# SCH_H-brug.net
KiCad netlist of a schematic drawn in EasyEDA
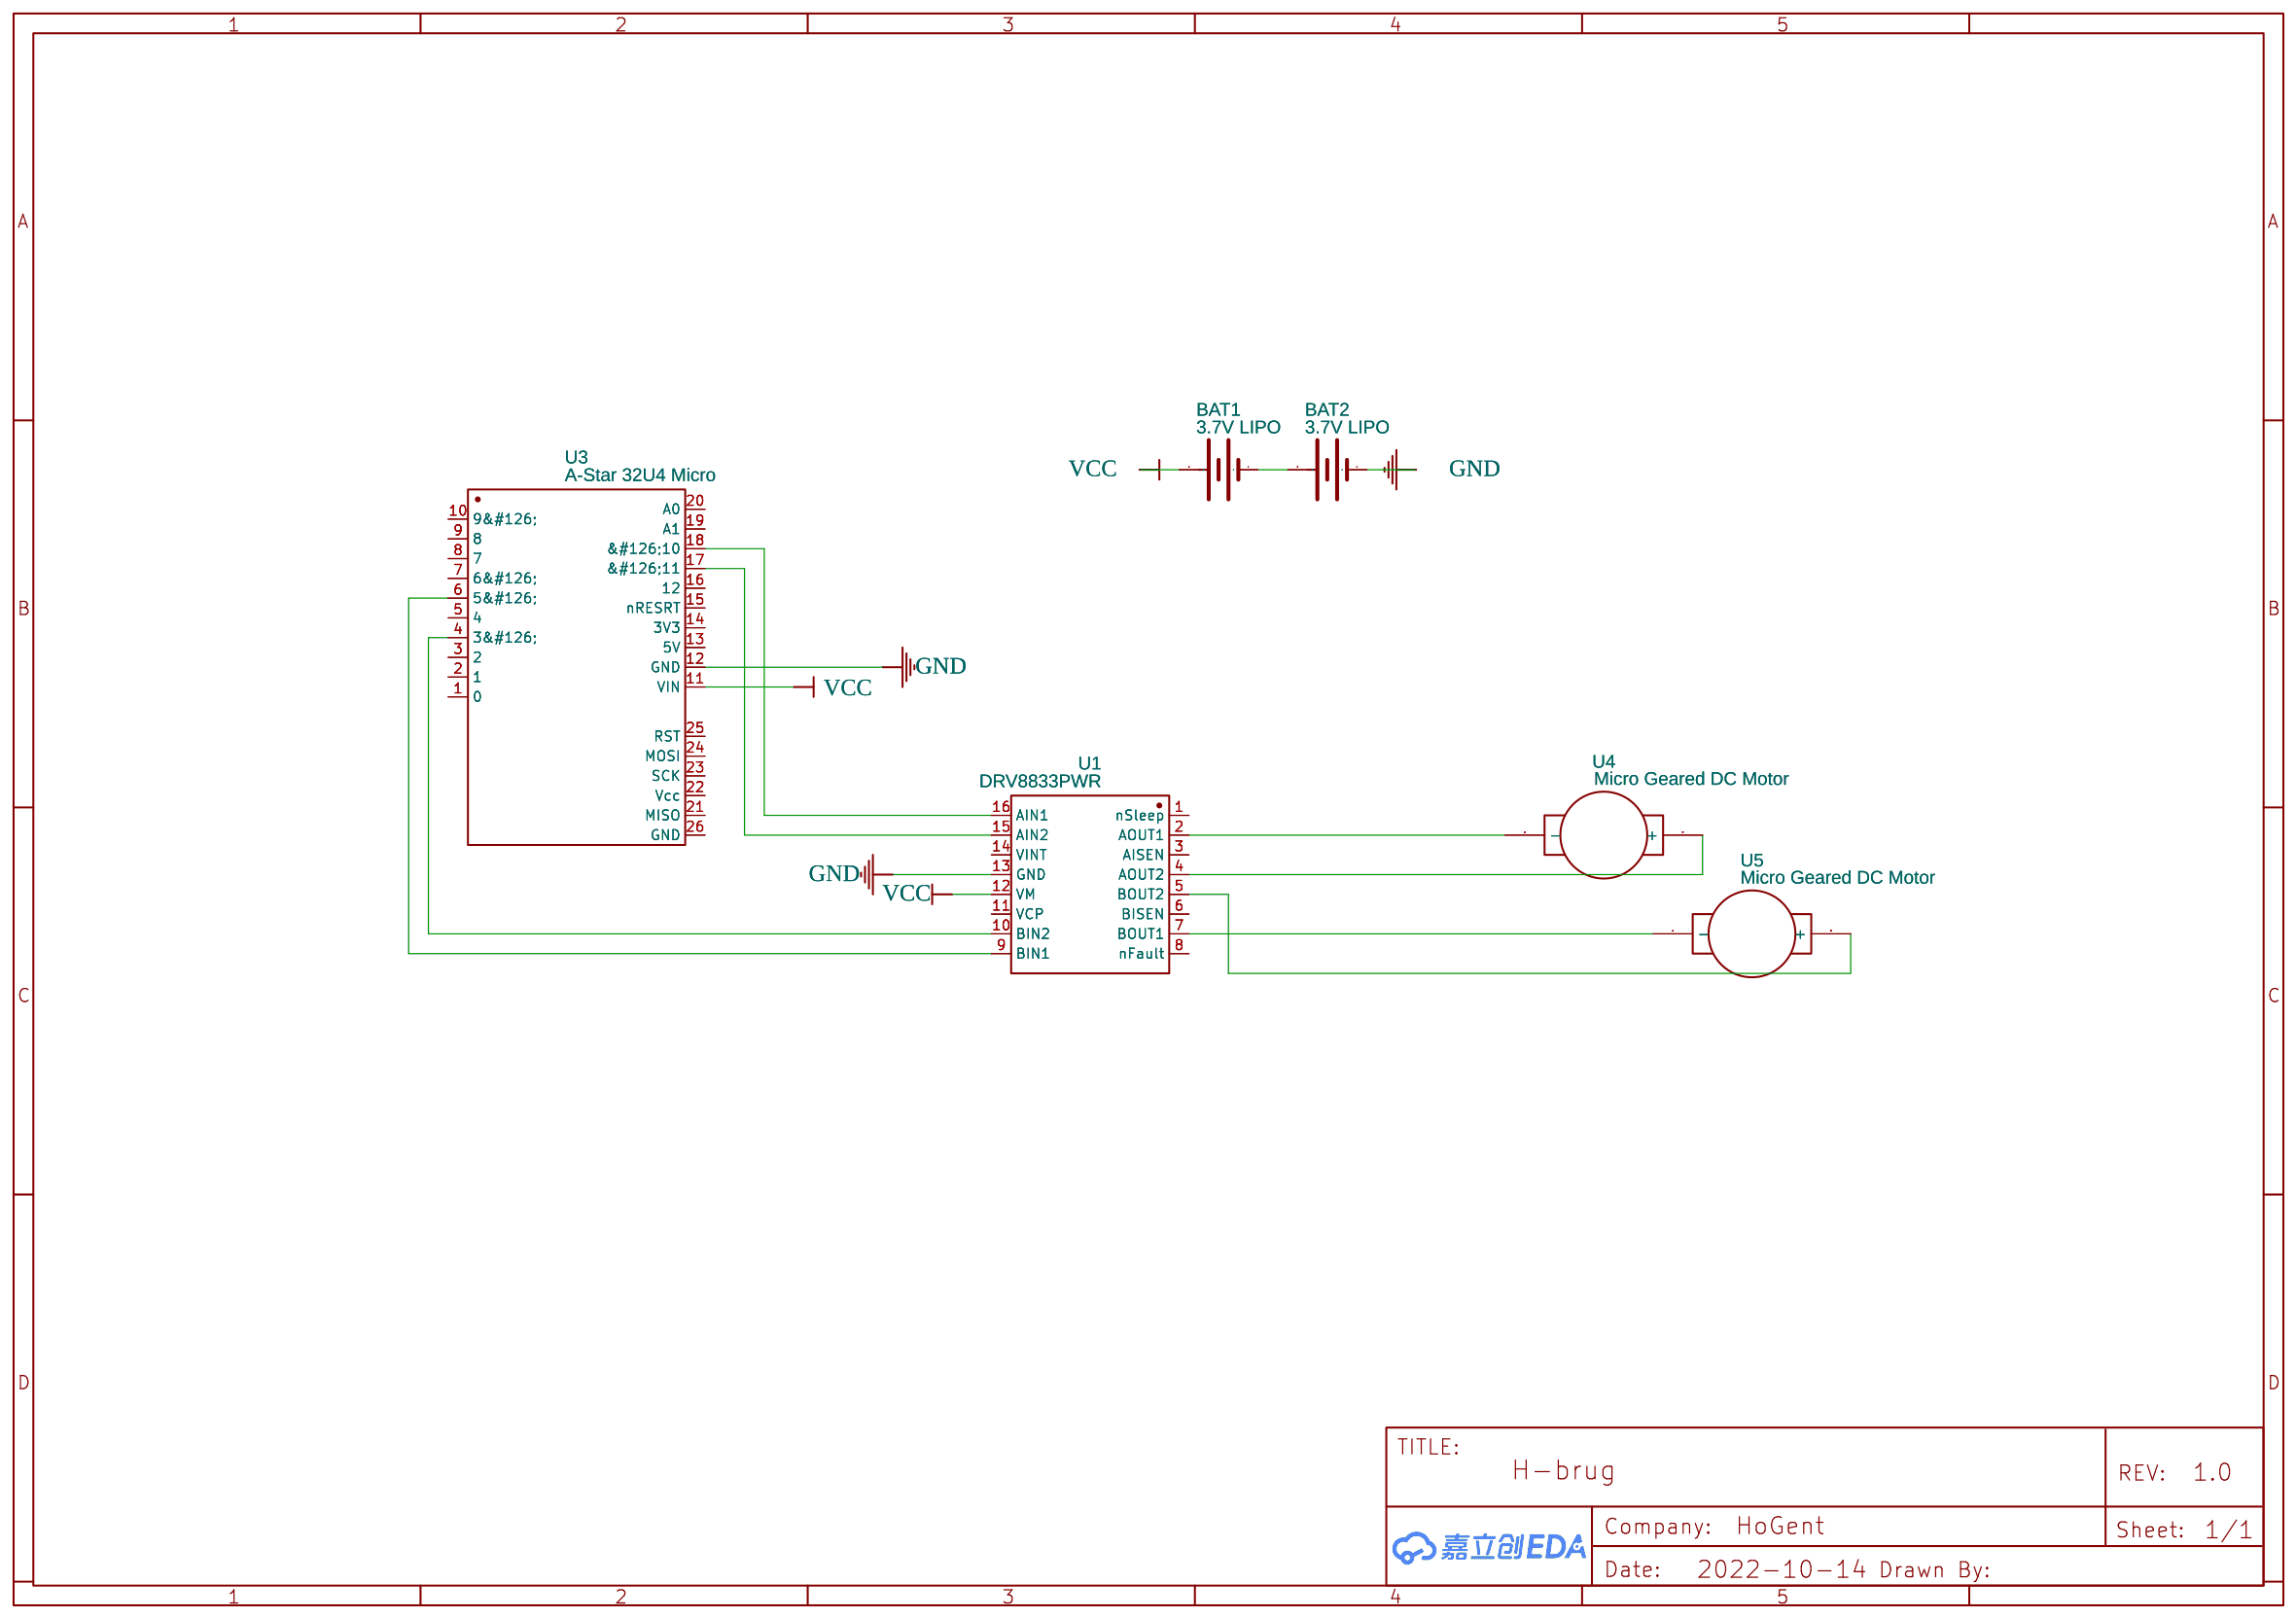
[diagram p0: schematic sheet]

(export (version "E")
  (design (tool "Eeschema 10.0.6"))
  (components
    (comp (ref "BAT1") (value "3.7V LIPO") (libsource (lib "") (part "3.7V LIPO")))
    (comp (ref "BAT2") (value "3.7V LIPO") (libsource (lib "") (part "3.7V LIPO")))
    (comp (ref "U1")
      (value "DRV8833PWR")
      (fields (field (name "BOM_Supplier Part") "C544801"))
      (libsource (lib "") (part "DRV8833PWR"))
    )
    (comp (ref "U3")
      (value "A-Star 32U4 Micro")
      (fields (field (name "BOM_Manufacturer Part") "3101"))
      (libsource (lib "") (part "A-Star 32U4 Micro"))
    )
    (comp (ref "U4") (value "Micro Geared DC Motor") (libsource (lib "") (part "Micro Geared DC Motor")))
    (comp (ref "U5") (value "Micro Geared DC Motor") (libsource (lib "") (part "Micro Geared DC Motor")))
  )
  (nets
    (net (code "1") (name "GND") (class "Default")
      (node (ref "BAT2") (pin "-") (pinfunction "-_-") (pintype "passive"))
      (node (ref "U1") (pin "13") (pinfunction "GND_13") (pintype "unspecified"))
      (node (ref "U3") (pin "12") (pinfunction "GND_12") (pintype "unspecified"))
    )
    (net (code "2") (name "Net-(BAT1-Pad-)") (class "Default")
      (node (ref "BAT1") (pin "-") (pinfunction "-_-") (pintype "passive"))
      (node (ref "BAT2") (pin "+") (pinfunction "+_+") (pintype "passive"))
    )
    (net (code "3") (name "Net-(U1-AIN1)") (class "Default")
      (node (ref "U1") (pin "16") (pinfunction "AIN1_16") (pintype "unspecified"))
      (node (ref "U3") (pin "18") (pinfunction "&#126;10_18") (pintype "unspecified"))
    )
    (net (code "4") (name "Net-(U1-AIN2)") (class "Default")
      (node (ref "U1") (pin "15") (pinfunction "AIN2_15") (pintype "unspecified"))
      (node (ref "U3") (pin "17") (pinfunction "&#126;11_17") (pintype "unspecified"))
    )
    (net (code "5") (name "Net-(U1-AOUT1)") (class "Default")
      (node (ref "U1") (pin "2") (pinfunction "AOUT1_2") (pintype "unspecified"))
      (node (ref "U4") (pin "1") (pinfunction "-_1") (pintype "unspecified"))
    )
    (net (code "6") (name "Net-(U1-AOUT2)") (class "Default")
      (node (ref "U1") (pin "4") (pinfunction "AOUT2_4") (pintype "unspecified"))
      (node (ref "U4") (pin "2") (pinfunction "+_2") (pintype "unspecified"))
    )
    (net (code "7") (name "Net-(U1-BIN1)") (class "Default")
      (node (ref "U1") (pin "9") (pinfunction "BIN1_9") (pintype "unspecified"))
      (node (ref "U3") (pin "6") (pinfunction "5&#126;_6") (pintype "unspecified"))
    )
    (net (code "8") (name "Net-(U1-BIN2)") (class "Default")
      (node (ref "U1") (pin "10") (pinfunction "BIN2_10") (pintype "unspecified"))
      (node (ref "U3") (pin "4") (pinfunction "3&#126;_4") (pintype "unspecified"))
    )
    (net (code "9") (name "Net-(U1-BOUT1)") (class "Default")
      (node (ref "U1") (pin "7") (pinfunction "BOUT1_7") (pintype "unspecified"))
      (node (ref "U5") (pin "1") (pinfunction "-_1") (pintype "unspecified"))
    )
    (net (code "10") (name "Net-(U1-BOUT2)") (class "Default")
      (node (ref "U1") (pin "5") (pinfunction "BOUT2_5") (pintype "unspecified"))
      (node (ref "U5") (pin "2") (pinfunction "+_2") (pintype "unspecified"))
    )
    (net (code "11") (name "VCC") (class "Default")
      (node (ref "BAT1") (pin "+") (pinfunction "+_+") (pintype "passive"))
      (node (ref "U1") (pin "12") (pinfunction "VM_12") (pintype "unspecified"))
      (node (ref "U3") (pin "11") (pinfunction "VIN_11") (pintype "unspecified"))
    )
    (net (code "12") (name "unconnected-(U1-AISEN-Pad3)") (class "Default")
      (node (ref "U1") (pin "3") (pinfunction "AISEN_3") (pintype "unspecified"))
    )
    (net (code "13") (name "unconnected-(U1-BISEN-Pad6)") (class "Default")
      (node (ref "U1") (pin "6") (pinfunction "BISEN_6") (pintype "unspecified"))
    )
    (net (code "14") (name "unconnected-(U1-VCP-Pad11)") (class "Default")
      (node (ref "U1") (pin "11") (pinfunction "VCP_11") (pintype "unspecified"))
    )
    (net (code "15") (name "unconnected-(U1-VINT-Pad14)") (class "Default")
      (node (ref "U1") (pin "14") (pinfunction "VINT_14") (pintype "unspecified"))
    )
    (net (code "16") (name "unconnected-(U1-nFault-Pad8)") (class "Default")
      (node (ref "U1") (pin "8") (pinfunction "nFault_8") (pintype "unspecified"))
    )
    (net (code "17") (name "unconnected-(U1-nSleep-Pad1)") (class "Default")
      (node (ref "U1") (pin "1") (pinfunction "nSleep_1") (pintype "unspecified"))
    )
    (net (code "18") (name "unconnected-(U3-0-Pad1)") (class "Default")
      (node (ref "U3") (pin "1") (pinfunction "0_1") (pintype "unspecified"))
    )
    (net (code "19") (name "unconnected-(U3-1-Pad2)") (class "Default")
      (node (ref "U3") (pin "2") (pinfunction "1_2") (pintype "unspecified"))
    )
    (net (code "20") (name "unconnected-(U3-2-Pad3)") (class "Default")
      (node (ref "U3") (pin "3") (pinfunction "2_3") (pintype "unspecified"))
    )
    (net (code "21") (name "unconnected-(U3-3V3-Pad14)") (class "Default")
      (node (ref "U3") (pin "14") (pinfunction "3V3_14") (pintype "unspecified"))
    )
    (net (code "22") (name "unconnected-(U3-4-Pad5)") (class "Default")
      (node (ref "U3") (pin "5") (pinfunction "4_5") (pintype "unspecified"))
    )
    (net (code "23") (name "unconnected-(U3-5V-Pad13)") (class "Default")
      (node (ref "U3") (pin "13") (pinfunction "5V_13") (pintype "unspecified"))
    )
    (net (code "24") (name "unconnected-(U3-6&#126;-Pad7)") (class "Default")
      (node (ref "U3") (pin "7") (pinfunction "6&#126;_7") (pintype "unspecified"))
    )
    (net (code "25") (name "unconnected-(U3-7-Pad8)") (class "Default")
      (node (ref "U3") (pin "8") (pinfunction "7_8") (pintype "unspecified"))
    )
    (net (code "26") (name "unconnected-(U3-8-Pad9)") (class "Default")
      (node (ref "U3") (pin "9") (pinfunction "8_9") (pintype "unspecified"))
    )
    (net (code "27") (name "unconnected-(U3-9&#126;-Pad10)") (class "Default")
      (node (ref "U3") (pin "10") (pinfunction "9&#126;_10") (pintype "unspecified"))
    )
    (net (code "28") (name "unconnected-(U3-12-Pad16)") (class "Default")
      (node (ref "U3") (pin "16") (pinfunction "12_16") (pintype "unspecified"))
    )
    (net (code "29") (name "unconnected-(U3-A0-Pad20)") (class "Default")
      (node (ref "U3") (pin "20") (pinfunction "A0_20") (pintype "unspecified"))
    )
    (net (code "30") (name "unconnected-(U3-A1-Pad19)") (class "Default")
      (node (ref "U3") (pin "19") (pinfunction "A1_19") (pintype "unspecified"))
    )
    (net (code "31") (name "unconnected-(U3-GND-Pad26)") (class "Default")
      (node (ref "U3") (pin "26") (pinfunction "GND_26") (pintype "unspecified"))
    )
    (net (code "32") (name "unconnected-(U3-MISO-Pad21)") (class "Default")
      (node (ref "U3") (pin "21") (pinfunction "MISO_21") (pintype "unspecified"))
    )
    (net (code "33") (name "unconnected-(U3-MOSI-Pad24)") (class "Default")
      (node (ref "U3") (pin "24") (pinfunction "MOSI_24") (pintype "unspecified"))
    )
    (net (code "34") (name "unconnected-(U3-RST-Pad25)") (class "Default")
      (node (ref "U3") (pin "25") (pinfunction "RST_25") (pintype "unspecified"))
    )
    (net (code "35") (name "unconnected-(U3-SCK-Pad23)") (class "Default")
      (node (ref "U3") (pin "23") (pinfunction "SCK_23") (pintype "unspecified"))
    )
    (net (code "36") (name "unconnected-(U3-Vcc-Pad22)") (class "Default")
      (node (ref "U3") (pin "22") (pinfunction "Vcc_22") (pintype "unspecified"))
    )
    (net (code "37") (name "unconnected-(U3-nRESRT-Pad15)") (class "Default")
      (node (ref "U3") (pin "15") (pinfunction "nRESRT_15") (pintype "unspecified"))
    )
  )
)
